# MCU_PCL.net
KiCad netlist of a schematic drawn in Altium Designer
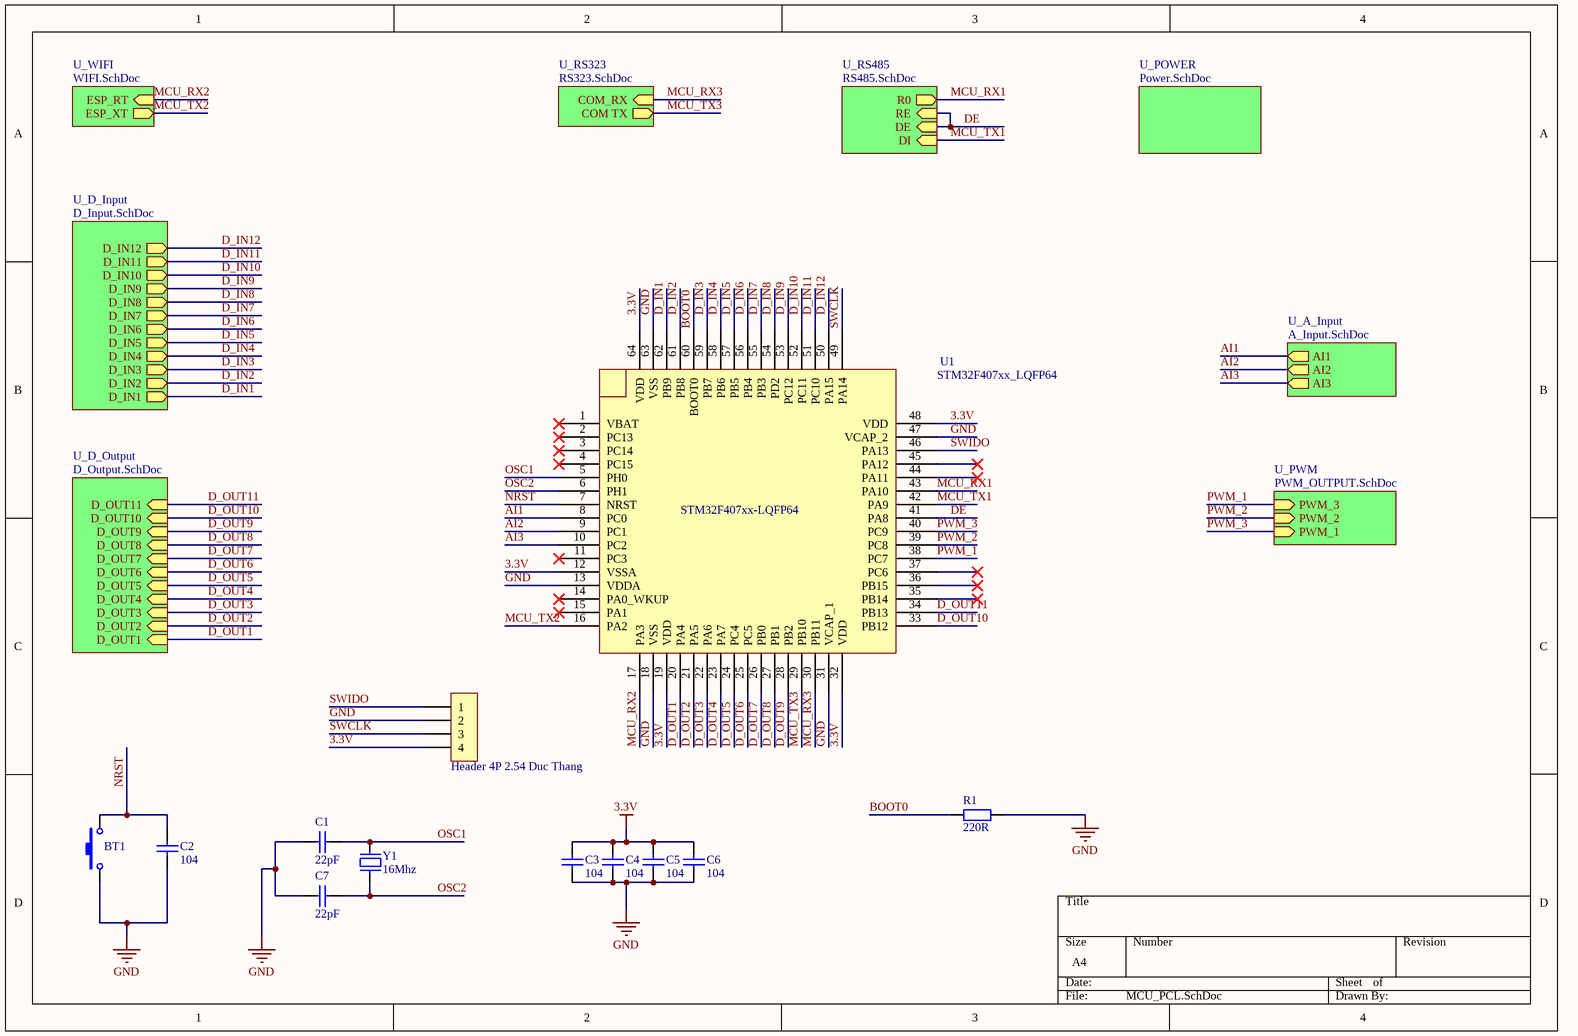
[diagram p0: MCU_PCL.SchDoc]

(export (version "E")
  (design (tool "Eeschema 10.0.6"))
  (components
    (comp (ref "BT1")
      (value "Nut Nhan 2 Chan SMD 3x6x2.5")
      (footprint "Nut Nhan 2 Chan SMD 3x6x2.5")
      (libsource (lib "Altium_Lib_by_KhueNguyenCreator") (part "Nut Nhan 2 Chan SMD 3x6x2.5"))
    )
    (comp (ref "C1")
      (value "22pF")
      (footprint "tu 0805")
      (description "Dán")
      (libsource (lib "Altium_Lib_by_KhueNguyenCreator") (part "Tu 0805 22pF 50V 10%"))
    )
    (comp (ref "C2")
      (value "104")
      (footprint "tu 0603")
      (description "Dán")
      (libsource (lib "Altium_Lib_by_KhueNguyenCreator") (part "Tu 0603 104 50V 10%"))
    )
    (comp (ref "C3")
      (value "104")
      (footprint "tu 0603")
      (description "Dán")
      (libsource (lib "Altium_Lib_by_KhueNguyenCreator") (part "Tu 0603 104 50V 10%"))
    )
    (comp (ref "C4")
      (value "104")
      (footprint "tu 0603")
      (description "Dán")
      (libsource (lib "Altium_Lib_by_KhueNguyenCreator") (part "Tu 0603 104 50V 10%"))
    )
    (comp (ref "C5")
      (value "104")
      (footprint "tu 0603")
      (description "Dán")
      (libsource (lib "Altium_Lib_by_KhueNguyenCreator") (part "Tu 0603 104 50V 10%"))
    )
    (comp (ref "C6")
      (value "104")
      (footprint "tu 0603")
      (description "Dán")
      (libsource (lib "Altium_Lib_by_KhueNguyenCreator") (part "Tu 0603 104 50V 10%"))
    )
    (comp (ref "C7")
      (value "22pF")
      (footprint "tu 0805")
      (description "Dán")
      (libsource (lib "Altium_Lib_by_KhueNguyenCreator") (part "Tu 0805 22pF 50V 10%"))
    )
    (comp (ref "H1")
      (value "Header 4P 2.54 Duc Thang")
      (footprint "XH2.54M-4")
      (description "Cắm")
      (libsource (lib "Altium_Lib_by_KhueNguyenCreator") (part "Header 4P 2.54 Duc Thang"))
    )
    (comp (ref "R1")
      (value "220R")
      (footprint "tro smd 0603")
      (description "Dán")
      (libsource (lib "Altium_Lib_by_KhueNguyenCreator") (part "Tro 0603 5% 220R"))
    )
    (comp (ref "U1")
      (value "STM32F407xx_LQFP64")
      (footprint "STM32_LQFP64")
      (libsource (lib "Altium_Lib_by_KhueNguyenCreator") (part "STM32F407xx_LQFP64"))
    )
    (comp (ref "Y1")
      (value "16Mhz")
      (footprint "Thach Anh 2 chan SMD")
      (description "Crystal For all Crystal 2pin.")
      (libsource (lib "Altium_Lib_by_KhueNguyenCreator") (part "Thach Anh 2 chan SMD"))
    )
  )
  (nets
    (net (code "2") (name "/AI1") (class "Default")
      (node (ref "U1") (pin "8") (pinfunction "PC0_8") (pintype "passive"))
    )
    (net (code "3") (name "/AI2") (class "Default")
      (node (ref "U1") (pin "9") (pinfunction "PC1_9") (pintype "passive"))
    )
    (net (code "4") (name "/AI3") (class "Default")
      (node (ref "U1") (pin "10") (pinfunction "PC2_10") (pintype "passive"))
    )
    (net (code "5") (name "/BOOT0") (class "Default")
      (node (ref "R1") (pin "1") (pinfunction "1_1") (pintype "passive"))
      (node (ref "U1") (pin "60") (pinfunction "BOOT0_60") (pintype "passive"))
    )
    (net (code "6") (name "/DE") (class "Default")
      (node (ref "U1") (pin "41") (pinfunction "PA8_41") (pintype "passive"))
    )
    (net (code "7") (name "/D_IN1") (class "Default")
      (node (ref "U1") (pin "62") (pinfunction "PB9_62") (pintype "passive"))
    )
    (net (code "8") (name "/D_IN2") (class "Default")
      (node (ref "U1") (pin "61") (pinfunction "PB8_61") (pintype "passive"))
    )
    (net (code "9") (name "/D_IN3") (class "Default")
      (node (ref "U1") (pin "59") (pinfunction "PB7_59") (pintype "passive"))
    )
    (net (code "10") (name "/D_IN4") (class "Default")
      (node (ref "U1") (pin "58") (pinfunction "PB6_58") (pintype "passive"))
    )
    (net (code "11") (name "/D_IN5") (class "Default")
      (node (ref "U1") (pin "57") (pinfunction "PB5_57") (pintype "passive"))
    )
    (net (code "12") (name "/D_IN6") (class "Default")
      (node (ref "U1") (pin "56") (pinfunction "PB4_56") (pintype "passive"))
    )
    (net (code "13") (name "/D_IN7") (class "Default")
      (node (ref "U1") (pin "55") (pinfunction "PB3_55") (pintype "passive"))
    )
    (net (code "14") (name "/D_IN8") (class "Default")
      (node (ref "U1") (pin "54") (pinfunction "PD2_54") (pintype "passive"))
    )
    (net (code "15") (name "/D_IN9") (class "Default")
      (node (ref "U1") (pin "53") (pinfunction "PC12_53") (pintype "passive"))
    )
    (net (code "16") (name "/D_IN10") (class "Default")
      (node (ref "U1") (pin "52") (pinfunction "PC11_52") (pintype "passive"))
    )
    (net (code "17") (name "/D_IN11") (class "Default")
      (node (ref "U1") (pin "51") (pinfunction "PC10_51") (pintype "passive"))
    )
    (net (code "18") (name "/D_IN12") (class "Default")
      (node (ref "U1") (pin "50") (pinfunction "PA15_50") (pintype "passive"))
    )
    (net (code "19") (name "/D_OUT1") (class "Default")
      (node (ref "U1") (pin "20") (pinfunction "PA4_20") (pintype "passive"))
    )
    (net (code "20") (name "/D_OUT2") (class "Default")
      (node (ref "U1") (pin "21") (pinfunction "PA5_21") (pintype "passive"))
    )
    (net (code "21") (name "/D_OUT3") (class "Default")
      (node (ref "U1") (pin "22") (pinfunction "PA6_22") (pintype "passive"))
    )
    (net (code "22") (name "/D_OUT4") (class "Default")
      (node (ref "U1") (pin "23") (pinfunction "PA7_23") (pintype "passive"))
    )
    (net (code "23") (name "/D_OUT5") (class "Default")
      (node (ref "U1") (pin "24") (pinfunction "PC4_24") (pintype "passive"))
    )
    (net (code "24") (name "/D_OUT6") (class "Default")
      (node (ref "U1") (pin "25") (pinfunction "PC5_25") (pintype "passive"))
    )
    (net (code "25") (name "/D_OUT7") (class "Default")
      (node (ref "U1") (pin "26") (pinfunction "PB0_26") (pintype "passive"))
    )
    (net (code "26") (name "/D_OUT8") (class "Default")
      (node (ref "U1") (pin "27") (pinfunction "PB1_27") (pintype "passive"))
    )
    (net (code "27") (name "/D_OUT9") (class "Default")
      (node (ref "U1") (pin "28") (pinfunction "PB2_28") (pintype "passive"))
    )
    (net (code "28") (name "/D_OUT10") (class "Default")
      (node (ref "U1") (pin "33") (pinfunction "PB12_33") (pintype "passive"))
    )
    (net (code "29") (name "/D_OUT11") (class "Default")
      (node (ref "U1") (pin "34") (pinfunction "PB13_34") (pintype "passive"))
    )
    (net (code "30") (name "/MCU_RX1") (class "Default")
      (node (ref "U1") (pin "43") (pinfunction "PA10_43") (pintype "passive"))
    )
    (net (code "31") (name "/MCU_RX2") (class "Default")
      (node (ref "U1") (pin "17") (pinfunction "PA3_17") (pintype "passive"))
    )
    (net (code "32") (name "/MCU_RX3") (class "Default")
      (node (ref "U1") (pin "30") (pinfunction "PB11_30") (pintype "passive"))
    )
    (net (code "33") (name "/MCU_TX1") (class "Default")
      (node (ref "U1") (pin "42") (pinfunction "PA9_42") (pintype "passive"))
    )
    (net (code "34") (name "/MCU_TX2") (class "Default")
      (node (ref "U1") (pin "16") (pinfunction "PA2_16") (pintype "passive"))
    )
    (net (code "35") (name "/MCU_TX3") (class "Default")
      (node (ref "U1") (pin "29") (pinfunction "PB10_29") (pintype "passive"))
    )
    (net (code "36") (name "/NRST") (class "Default")
      (node (ref "BT1") (pin "2") (pinfunction "2_2") (pintype "passive"))
      (node (ref "C2") (pin "1") (pinfunction "1_1") (pintype "passive"))
      (node (ref "U1") (pin "7") (pinfunction "NRST_7") (pintype "passive"))
    )
    (net (code "37") (name "/OSC1") (class "Default")
      (node (ref "C1") (pin "2") (pinfunction "2_2") (pintype "passive"))
      (node (ref "U1") (pin "5") (pinfunction "PH0_5") (pintype "passive"))
      (node (ref "Y1") (pin "2") (pinfunction "2_2") (pintype "passive"))
    )
    (net (code "38") (name "/OSC2") (class "Default")
      (node (ref "C7") (pin "2") (pinfunction "2_2") (pintype "passive"))
      (node (ref "U1") (pin "6") (pinfunction "PH1_6") (pintype "passive"))
      (node (ref "Y1") (pin "1") (pinfunction "1_1") (pintype "passive"))
    )
    (net (code "39") (name "/PWM_1") (class "Default")
      (node (ref "U1") (pin "38") (pinfunction "PC7_38") (pintype "passive"))
    )
    (net (code "40") (name "/PWM_2") (class "Default")
      (node (ref "U1") (pin "39") (pinfunction "PC8_39") (pintype "passive"))
    )
    (net (code "41") (name "/PWM_3") (class "Default")
      (node (ref "U1") (pin "40") (pinfunction "PC9_40") (pintype "passive"))
    )
    (net (code "42") (name "/SWCLK") (class "Default")
      (node (ref "H1") (pin "3") (pinfunction "3_3") (pintype "passive"))
      (node (ref "U1") (pin "49") (pinfunction "PA14_49") (pintype "passive"))
    )
    (net (code "43") (name "/SWIDO") (class "Default")
      (node (ref "H1") (pin "1") (pinfunction "1_1") (pintype "passive"))
      (node (ref "U1") (pin "46") (pinfunction "PA13_46") (pintype "passive"))
    )
    (net (code "44") (name "3.3V") (class "Default")
      (node (ref "C3") (pin "1") (pinfunction "1_1") (pintype "passive"))
      (node (ref "C4") (pin "1") (pinfunction "1_1") (pintype "passive"))
      (node (ref "C5") (pin "1") (pinfunction "1_1") (pintype "passive"))
      (node (ref "C6") (pin "1") (pinfunction "1_1") (pintype "passive"))
      (node (ref "H1") (pin "4") (pinfunction "4_4") (pintype "passive"))
      (node (ref "U1") (pin "12") (pinfunction "VSSA_12") (pintype "passive"))
      (node (ref "U1") (pin "19") (pinfunction "VDD_19") (pintype "passive"))
      (node (ref "U1") (pin "32") (pinfunction "VDD_32") (pintype "passive"))
      (node (ref "U1") (pin "48") (pinfunction "VDD_48") (pintype "passive"))
      (node (ref "U1") (pin "64") (pinfunction "VDD_64") (pintype "passive"))
    )
    (net (code "45") (name "GND") (class "Default")
      (node (ref "BT1") (pin "1") (pinfunction "1_1") (pintype "passive"))
      (node (ref "C1") (pin "1") (pinfunction "1_1") (pintype "passive"))
      (node (ref "C2") (pin "2") (pinfunction "2_2") (pintype "passive"))
      (node (ref "C3") (pin "2") (pinfunction "2_2") (pintype "passive"))
      (node (ref "C4") (pin "2") (pinfunction "2_2") (pintype "passive"))
      (node (ref "C5") (pin "2") (pinfunction "2_2") (pintype "passive"))
      (node (ref "C6") (pin "2") (pinfunction "2_2") (pintype "passive"))
      (node (ref "C7") (pin "1") (pinfunction "1_1") (pintype "passive"))
      (node (ref "H1") (pin "2") (pinfunction "2_2") (pintype "passive"))
      (node (ref "R1") (pin "2") (pinfunction "2_2") (pintype "passive"))
      (node (ref "U1") (pin "13") (pinfunction "VDDA_13") (pintype "passive"))
      (node (ref "U1") (pin "18") (pinfunction "VSS_18") (pintype "passive"))
      (node (ref "U1") (pin "31") (pinfunction "VCAP_1_31") (pintype "passive"))
      (node (ref "U1") (pin "47") (pinfunction "VCAP_2_47") (pintype "passive"))
      (node (ref "U1") (pin "63") (pinfunction "VSS_63") (pintype "passive"))
    )
    (net (code "46") (name "unconnected-(U1-PA0_WKUP-Pad14)") (class "Default")
      (node (ref "U1") (pin "14") (pinfunction "PA0_WKUP_14") (pintype "passive+no_connect"))
    )
    (net (code "47") (name "unconnected-(U1-PA1-Pad15)") (class "Default")
      (node (ref "U1") (pin "15") (pinfunction "PA1_15") (pintype "passive+no_connect"))
    )
    (net (code "48") (name "unconnected-(U1-PA11-Pad44)") (class "Default")
      (node (ref "U1") (pin "44") (pinfunction "PA11_44") (pintype "passive+no_connect"))
    )
    (net (code "49") (name "unconnected-(U1-PA12-Pad45)") (class "Default")
      (node (ref "U1") (pin "45") (pinfunction "PA12_45") (pintype "passive+no_connect"))
    )
    (net (code "50") (name "unconnected-(U1-PB14-Pad35)") (class "Default")
      (node (ref "U1") (pin "35") (pinfunction "PB14_35") (pintype "passive+no_connect"))
    )
    (net (code "51") (name "unconnected-(U1-PB15-Pad36)") (class "Default")
      (node (ref "U1") (pin "36") (pinfunction "PB15_36") (pintype "passive+no_connect"))
    )
    (net (code "52") (name "unconnected-(U1-PC3-Pad11)") (class "Default")
      (node (ref "U1") (pin "11") (pinfunction "PC3_11") (pintype "passive+no_connect"))
    )
    (net (code "53") (name "unconnected-(U1-PC6-Pad37)") (class "Default")
      (node (ref "U1") (pin "37") (pinfunction "PC6_37") (pintype "passive+no_connect"))
    )
    (net (code "54") (name "unconnected-(U1-PC13-Pad2)") (class "Default")
      (node (ref "U1") (pin "2") (pinfunction "PC13_2") (pintype "passive+no_connect"))
    )
    (net (code "55") (name "unconnected-(U1-PC14-Pad3)") (class "Default")
      (node (ref "U1") (pin "3") (pinfunction "PC14_3") (pintype "passive+no_connect"))
    )
    (net (code "56") (name "unconnected-(U1-PC15-Pad4)") (class "Default")
      (node (ref "U1") (pin "4") (pinfunction "PC15_4") (pintype "passive+no_connect"))
    )
    (net (code "57") (name "unconnected-(U1-VBAT-Pad1)") (class "Default")
      (node (ref "U1") (pin "1") (pinfunction "VBAT_1") (pintype "passive+no_connect"))
    )
  )
)
